# Esquematico.net
KiCad netlist of a schematic drawn in Altium Designer
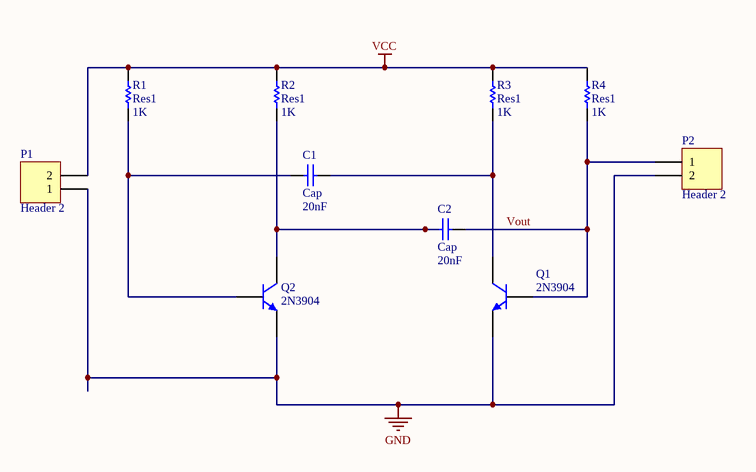
[diagram p0: Esquematico.SchDoc]

(export (version "E")
  (design (tool "Eeschema 10.0.6"))
  (components
    (comp (ref "C1")
      (value "Cap")
      (footprint "RAD-0.1")
      (description "Capacitor")
      (fields (field (name "ALTIUM_VALUE") "20nF") (field (name "PUBLISHER") "Altium Limited"))
      (libsource (lib "Miscellaneous Devices") (part "Cap"))
    )
    (comp (ref "C2")
      (value "Cap")
      (footprint "RAD-0.1")
      (description "Capacitor")
      (fields (field (name "ALTIUM_VALUE") "20nF") (field (name "PUBLISHER") "Altium Limited"))
      (libsource (lib "Miscellaneous Devices") (part "Cap"))
    )
    (comp (ref "P1")
      (value "Header 2")
      (footprint "HDR1X2")
      (description "Header, 2-Pin")
      (fields (field (name "PUBLISHER") "Altium Limited"))
      (libsource (lib "") (part "Header 2_1"))
    )
    (comp (ref "P2")
      (value "Header 2")
      (footprint "HDR1X2")
      (description "Header, 2-Pin")
      (fields (field (name "PUBLISHER") "Altium Limited"))
      (libsource (lib "Miscellaneous Connectors") (part "Header 2"))
    )
    (comp (ref "Q1")
      (value "2N3904")
      (footprint "TO-92A")
      (description "NPN General Purpose Amplifier")
      (fields (field (name "PUBLISHER") "Altium Limited"))
      (libsource (lib "Miscellaneous Devices") (part "2N3904"))
    )
    (comp (ref "Q2")
      (value "2N3904")
      (footprint "TO-92A")
      (description "NPN General Purpose Amplifier")
      (fields (field (name "PUBLISHER") "Altium Limited"))
      (libsource (lib "Miscellaneous Devices") (part "2N3904"))
    )
    (comp (ref "R1")
      (value "Res1")
      (footprint "AXIAL-0.3")
      (description "Resistor")
      (fields (field (name "ALTIUM_VALUE") "1K") (field (name "PUBLISHER") "Altium Limited"))
      (libsource (lib "Miscellaneous Devices") (part "Res1"))
    )
    (comp (ref "R2")
      (value "Res1")
      (footprint "AXIAL-0.3")
      (description "Resistor")
      (fields (field (name "ALTIUM_VALUE") "1K") (field (name "PUBLISHER") "Altium Limited"))
      (libsource (lib "Miscellaneous Devices") (part "Res1"))
    )
    (comp (ref "R3")
      (value "Res1")
      (footprint "AXIAL-0.3")
      (description "Resistor")
      (fields (field (name "ALTIUM_VALUE") "1K") (field (name "PUBLISHER") "Altium Limited"))
      (libsource (lib "Miscellaneous Devices") (part "Res1"))
    )
    (comp (ref "R4")
      (value "Res1")
      (footprint "AXIAL-0.3")
      (description "Resistor")
      (fields (field (name "ALTIUM_VALUE") "1K") (field (name "PUBLISHER") "Altium Limited"))
      (libsource (lib "Miscellaneous Devices") (part "Res1"))
    )
  )
  (nets
    (net (code "1") (name "/Vout") (class "Default")
      (node (ref "C2") (pin "1") (pinfunction "1_1") (pintype "passive"))
      (node (ref "P2") (pin "1") (pinfunction "1_1") (pintype "passive"))
      (node (ref "Q1") (pin "2") (pinfunction "B_2") (pintype "passive"))
      (node (ref "R4") (pin "1") (pinfunction "1_1") (pintype "passive"))
    )
    (net (code "2") (name "GND") (class "Default")
      (node (ref "P1") (pin "1") (pinfunction "1_1") (pintype "passive"))
      (node (ref "P2") (pin "2") (pinfunction "2_2") (pintype "passive"))
      (node (ref "Q1") (pin "1") (pinfunction "E_1") (pintype "passive"))
      (node (ref "Q2") (pin "1") (pinfunction "E_1") (pintype "passive"))
    )
    (net (code "3") (name "Net-(Q1-C)") (class "Default")
      (node (ref "C1") (pin "2") (pinfunction "2_2") (pintype "passive"))
      (node (ref "Q1") (pin "3") (pinfunction "C_3") (pintype "passive"))
      (node (ref "R3") (pin "1") (pinfunction "1_1") (pintype "passive"))
    )
    (net (code "4") (name "Net-(Q2-B)") (class "Default")
      (node (ref "C1") (pin "1") (pinfunction "1_1") (pintype "passive"))
      (node (ref "Q2") (pin "2") (pinfunction "B_2") (pintype "passive"))
      (node (ref "R1") (pin "1") (pinfunction "1_1") (pintype "passive"))
    )
    (net (code "5") (name "Net-(Q2-C)") (class "Default")
      (node (ref "C2") (pin "2") (pinfunction "2_2") (pintype "passive"))
      (node (ref "Q2") (pin "3") (pinfunction "C_3") (pintype "passive"))
      (node (ref "R2") (pin "1") (pinfunction "1_1") (pintype "passive"))
    )
    (net (code "6") (name "VCC") (class "Default")
      (node (ref "P1") (pin "2") (pinfunction "2_2") (pintype "passive"))
      (node (ref "R1") (pin "2") (pinfunction "2_2") (pintype "passive"))
      (node (ref "R2") (pin "2") (pinfunction "2_2") (pintype "passive"))
      (node (ref "R3") (pin "2") (pinfunction "2_2") (pintype "passive"))
      (node (ref "R4") (pin "2") (pinfunction "2_2") (pintype "passive"))
    )
  )
)
